# ads1118.net
KiCad netlist of a schematic drawn in Altium Designer
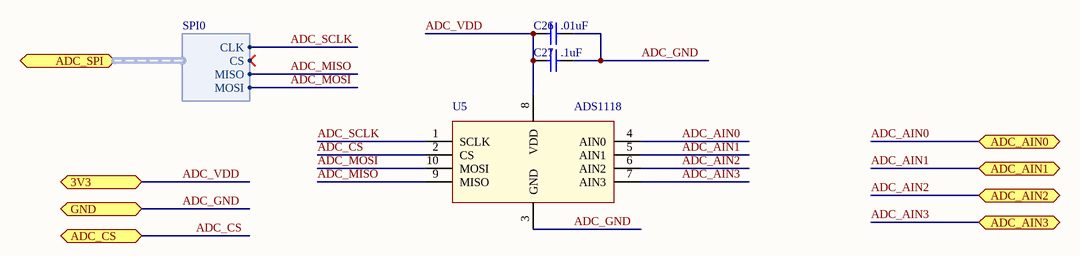
[diagram p0: ads1118.SchDoc]

(export (version "E")
  (design (tool "Eeschema 10.0.6"))
  (components
    (comp (ref "C26")
      (value ".01uF")
      (footprint "0805")
      (fields (field (name "TOLERANCE") "5%") (field (name "VOLTAGE") "10V") (field (name "Comment") "CAP"))
      (libsource (lib "gasctrl") (part "CAP"))
    )
    (comp (ref "C27")
      (value ".1uF")
      (footprint "0805")
      (fields (field (name "TOLERANCE") "5%") (field (name "VOLTAGE") "10V") (field (name "Comment") "CAP"))
      (libsource (lib "gasctrl") (part "CAP"))
    )
    (comp (ref "U5")
      (value "ADS1118")
      (footprint "TSSOP50P490X110-10N")
      (description "ADC for precision thermocouples")
      (fields (field (name "MANUFACTURER") "TI"))
      (libsource (lib "gasctrl") (part "ADS1118"))
    )
  )
  (nets
    (net (code "2") (name "/ADC_AIN0") (class "Default")
      (node (ref "U5") (pin "4") (pinfunction "AIN0_4") (pintype "passive"))
    )
    (net (code "3") (name "/ADC_AIN1") (class "Default")
      (node (ref "U5") (pin "5") (pinfunction "AIN1_5") (pintype "passive"))
    )
    (net (code "4") (name "/ADC_AIN2") (class "Default")
      (node (ref "U5") (pin "6") (pinfunction "AIN2_6") (pintype "passive"))
    )
    (net (code "5") (name "/ADC_AIN3") (class "Default")
      (node (ref "U5") (pin "7") (pinfunction "AIN3_7") (pintype "passive"))
    )
    (net (code "6") (name "/ADC_CS") (class "Default")
      (node (ref "U5") (pin "2") (pinfunction "CS_2") (pintype "passive"))
    )
    (net (code "7") (name "/ADC_GND") (class "Default")
      (node (ref "C26") (pin "1") (pinfunction "1_1") (pintype "passive"))
      (node (ref "C27") (pin "1") (pinfunction "1_1") (pintype "passive"))
      (node (ref "U5") (pin "3") (pinfunction "GND_3") (pintype "passive"))
    )
    (net (code "8") (name "/ADC_MISO") (class "Default")
      (node (ref "U5") (pin "9") (pinfunction "MISO_9") (pintype "passive"))
    )
    (net (code "9") (name "/ADC_MOSI") (class "Default")
      (node (ref "U5") (pin "10") (pinfunction "MOSI_10") (pintype "passive"))
    )
    (net (code "10") (name "/ADC_SCLK") (class "Default")
      (node (ref "U5") (pin "1") (pinfunction "SCLK_1") (pintype "passive"))
    )
    (net (code "11") (name "/ADC_VDD") (class "Default")
      (node (ref "C26") (pin "2") (pinfunction "2_2") (pintype "passive"))
      (node (ref "C27") (pin "2") (pinfunction "2_2") (pintype "passive"))
      (node (ref "U5") (pin "8") (pinfunction "VDD_8") (pintype "passive"))
    )
  )
)
